# BW1098FFC_USB.net
KiCad netlist of a schematic drawn in Altium Designer
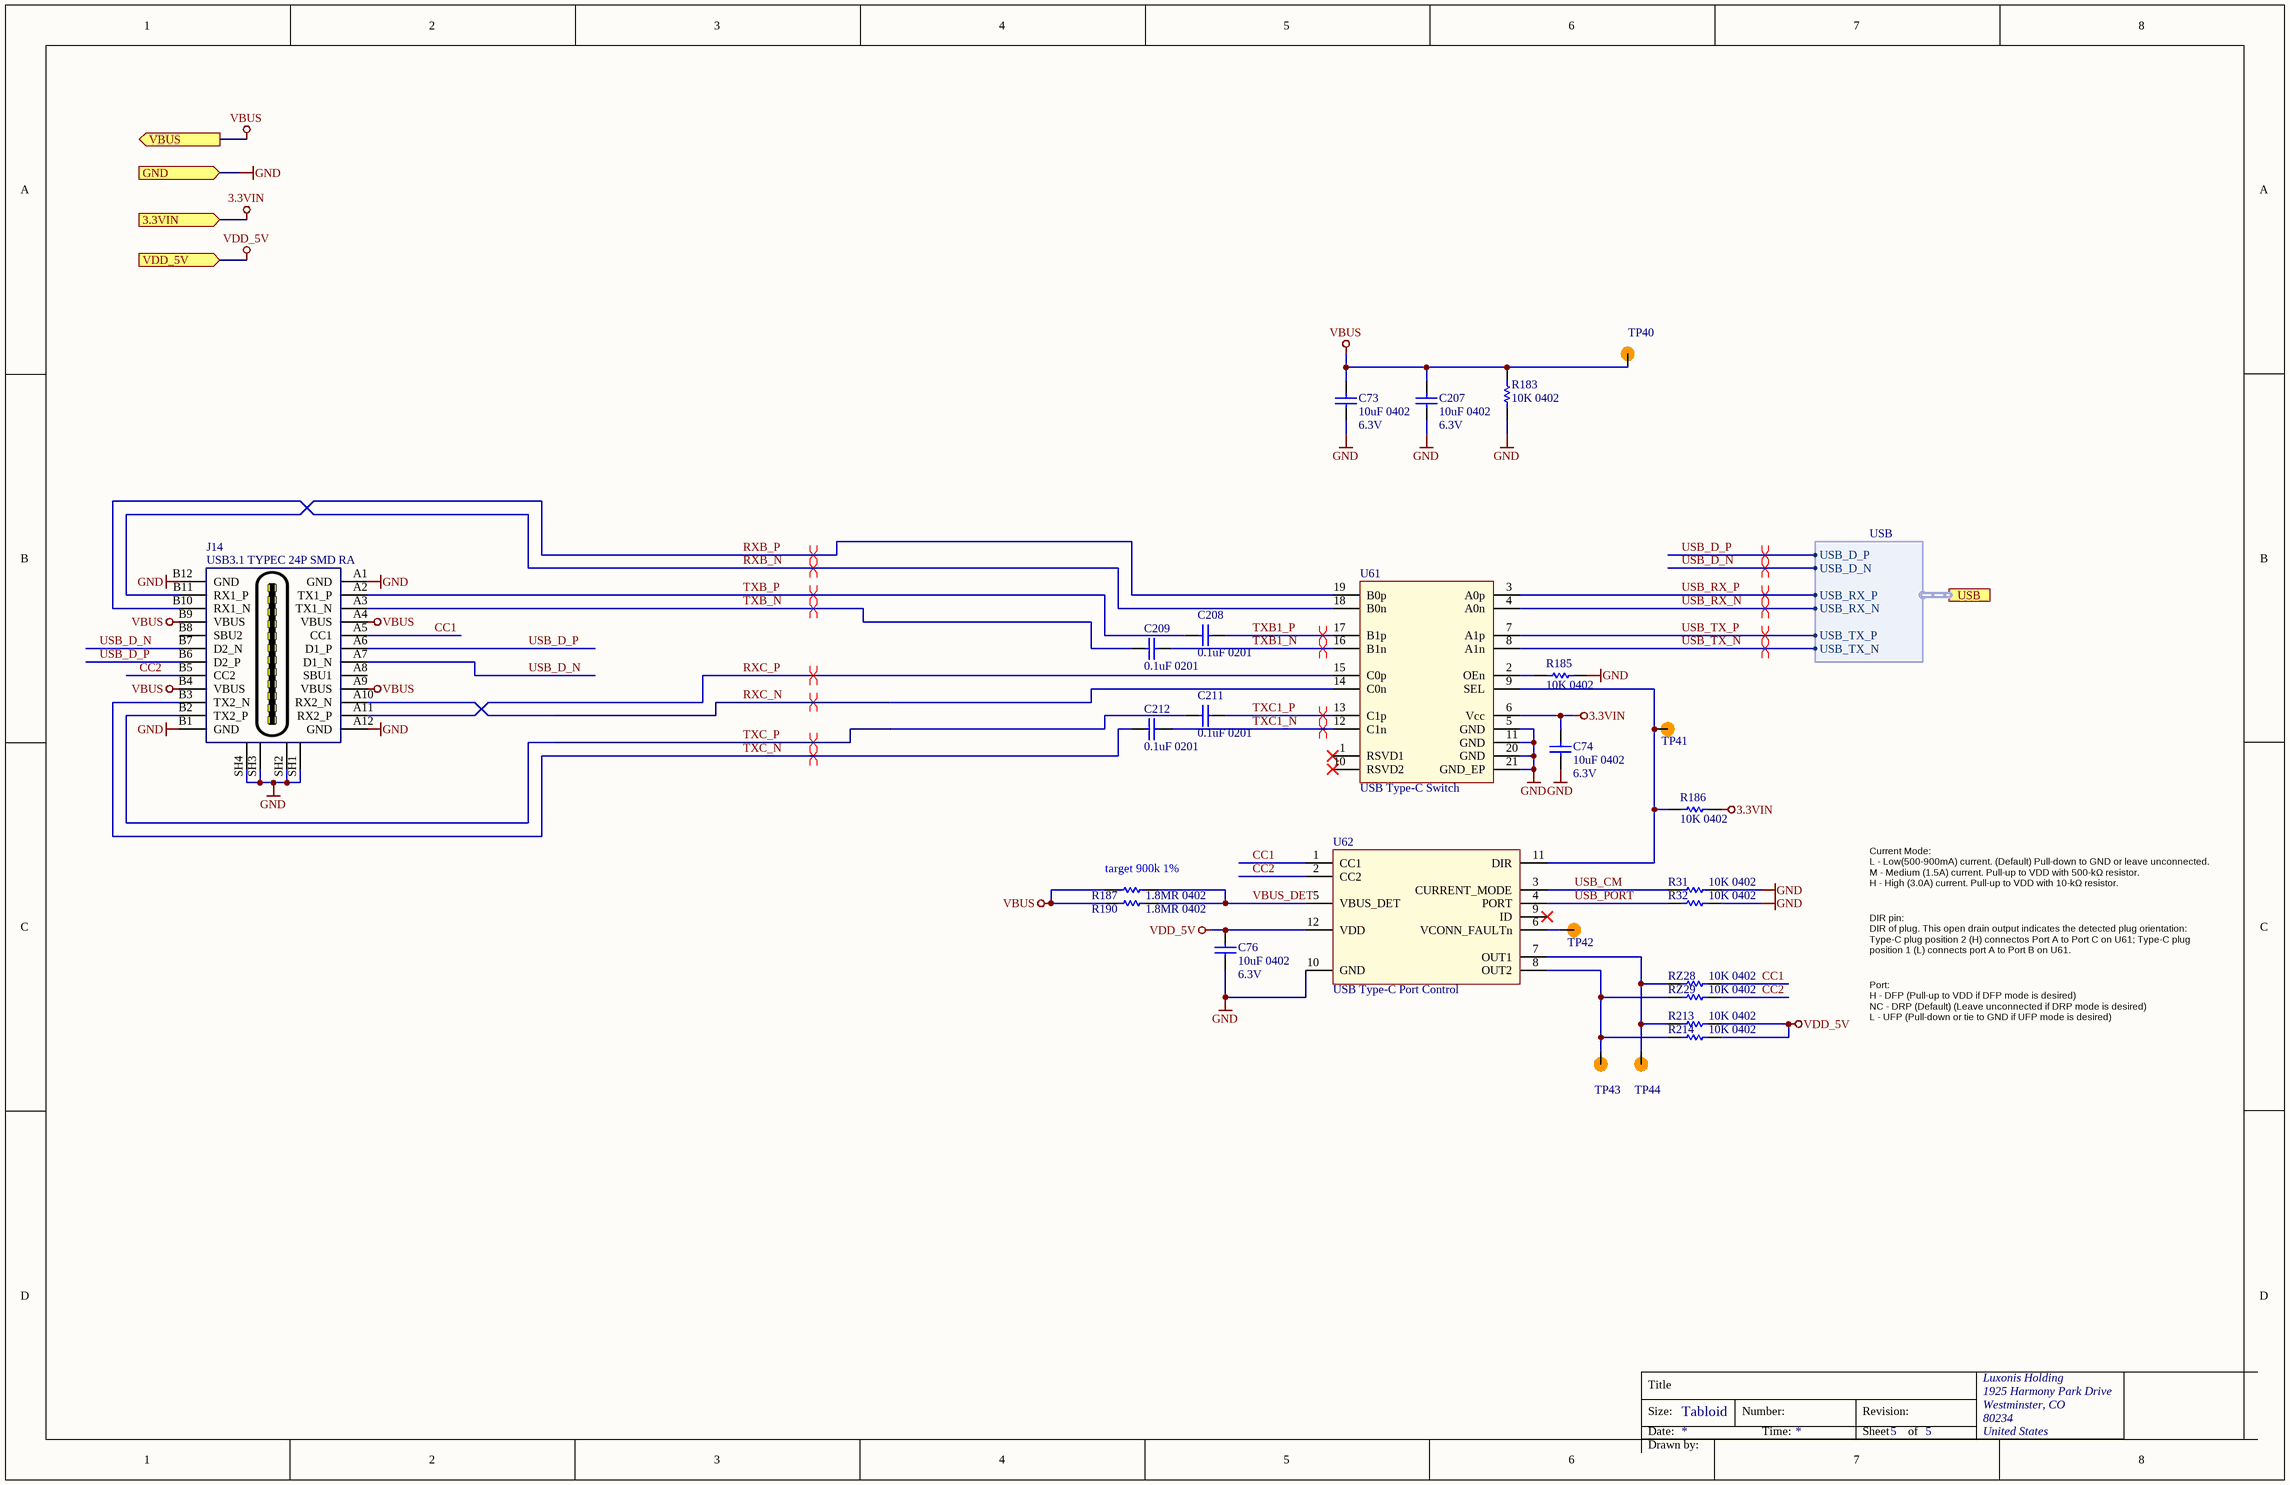
[diagram p0: BW1098FFC_USB.SchDoc]

(export (version "E")
  (design (tool "Eeschema 10.0.6"))
  (components
    (comp (ref "C73")
      (value "10uF 0402")
      (footprint "CAP_Altium_Vault_Generic:CAPC0402(1005)70_N")
      (description "CAP CER 10UF 6.3V X5R 0402 20%")
      (fields (field (name "TOLERANCE") "20%") (field (name "VOLTAGE RATING") "6.3V"))
      (libsource (lib "LuxonisMaster") (part "GRM155R60J106ME15D"))
    )
    (comp (ref "C74")
      (value "10uF 0402")
      (footprint "CAP_Altium_Vault_Generic:CAPC0402(1005)70_N")
      (description "CAP CER 10UF 6.3V X5R 0402 20%")
      (fields (field (name "TOLERANCE") "20%") (field (name "VOLTAGE RATING") "6.3V"))
      (libsource (lib "LuxonisMaster") (part "GRM155R60J106ME15D"))
    )
    (comp (ref "C76")
      (value "10uF 0402")
      (footprint "CAP_Altium_Vault_Generic:CAPC0402(1005)70_N")
      (description "CAP CER 10UF 6.3V X5R 0402 20%")
      (fields (field (name "TOLERANCE") "20%") (field (name "VOLTAGE RATING") "6.3V"))
      (libsource (lib "LuxonisMaster") (part "GRM155R60J106ME15D"))
    )
    (comp (ref "C207")
      (value "10uF 0402")
      (footprint "CAP_Altium_Vault_Generic:CAPC0402(1005)70_N")
      (description "CAP CER 10UF 6.3V X5R 0402 20%")
      (fields (field (name "TOLERANCE") "20%") (field (name "VOLTAGE RATING") "6.3V"))
      (libsource (lib "LuxonisMaster") (part "GRM155R60J106ME15D"))
    )
    (comp (ref "C208")
      (value "0.1uF 0201")
      (footprint "CAP_Altium_Vault_Generic:CAPC0201(0603)33_L")
      (description "CAP CER 0.1UF 10V X5R 0201")
      (fields (field (name "TOLERANCE") "10%") (field (name "VOLTAGE") "10V"))
      (libsource (lib "LuxonisMaster") (part "GRM033R61A104KE15D"))
    )
    (comp (ref "C209")
      (value "0.1uF 0201")
      (footprint "CAP_Altium_Vault_Generic:CAPC0201(0603)33_L")
      (description "CAP CER 0.1UF 10V X5R 0201")
      (fields (field (name "TOLERANCE") "10%") (field (name "VOLTAGE") "10V"))
      (libsource (lib "LuxonisMaster") (part "GRM033R61A104KE15D"))
    )
    (comp (ref "C211")
      (value "0.1uF 0201")
      (footprint "CAP_Altium_Vault_Generic:CAPC0201(0603)33_L")
      (description "CAP CER 0.1UF 10V X5R 0201")
      (fields (field (name "TOLERANCE") "10%") (field (name "VOLTAGE") "10V"))
      (libsource (lib "LuxonisMaster") (part "GRM033R61A104KE15D"))
    )
    (comp (ref "C212")
      (value "0.1uF 0201")
      (footprint "CAP_Altium_Vault_Generic:CAPC0201(0603)33_L")
      (description "CAP CER 0.1UF 10V X5R 0201")
      (fields (field (name "TOLERANCE") "10%") (field (name "VOLTAGE") "10V"))
      (libsource (lib "LuxonisMaster") (part "GRM033R61A104KE15D"))
    )
    (comp (ref "J14")
      (value "USB3.1 TYPEC 24P SMD RA")
      (footprint "LuxonisMaster:105450-0101")
      (description "CONN RCP USB3.1 TYPEC 24P SMD RA")
      (libsource (lib "LuxonisMaster") (part "105450-0101"))
    )
    (comp (ref "R31")
      (value "10K 0402")
      (footprint "RES_Altium_Vault_Generic:RESC0402(1005)_N")
      (fields (field (name "TOLERANCE") "1%"))
      (libsource (lib "LuxonisMaster") (part "RC0402FR-1310KL"))
    )
    (comp (ref "R32")
      (value "10K 0402")
      (footprint "RES_Altium_Vault_Generic:RESC0402(1005)_N")
      (fields (field (name "TOLERANCE") "1%"))
      (libsource (lib "LuxonisMaster") (part "RC0402FR-1310KL"))
    )
    (comp (ref "R183")
      (value "10K 0402")
      (footprint "RES_Altium_Vault_Generic:RESC0402(1005)_N")
      (fields (field (name "TOLERANCE") "1%"))
      (libsource (lib "LuxonisMaster") (part "RC0402FR-1310KL"))
    )
    (comp (ref "R185")
      (value "10K 0402")
      (footprint "RES_Altium_Vault_Generic:RESC0402(1005)_N")
      (fields (field (name "TOLERANCE") "1%"))
      (libsource (lib "LuxonisMaster") (part "RC0402FR-1310KL"))
    )
    (comp (ref "R186")
      (value "10K 0402")
      (footprint "RES_Altium_Vault_Generic:RESC0402(1005)_N")
      (fields (field (name "TOLERANCE") "1%"))
      (libsource (lib "LuxonisMaster") (part "RC0402FR-1310KL"))
    )
    (comp (ref "R187")
      (value "1.8MR 0402")
      (footprint "RES_Altium_Vault_Generic:RESC0402(1005)_N")
      (description "RES SMD 1.8M OHM 1% 1/16W 0402")
      (fields (field (name "TOLERANCE") "1%"))
      (libsource (lib "LuxonisMaster") (part "CRCW04021M80FKED"))
    )
    (comp (ref "R190")
      (value "1.8MR 0402")
      (footprint "RES_Altium_Vault_Generic:RESC0402(1005)_N")
      (description "RES SMD 1.8M OHM 1% 1/16W 0402")
      (fields (field (name "TOLERANCE") "1%"))
      (libsource (lib "LuxonisMaster") (part "CRCW04021M80FKED"))
    )
    (comp (ref "R213")
      (value "10K 0402")
      (footprint "RES_Altium_Vault_Generic:RESC0402(1005)_N")
      (fields (field (name "TOLERANCE") "1%"))
      (libsource (lib "LuxonisMaster") (part "RC0402FR-1310KL"))
    )
    (comp (ref "R214")
      (value "10K 0402")
      (footprint "RES_Altium_Vault_Generic:RESC0402(1005)_N")
      (fields (field (name "TOLERANCE") "1%"))
      (libsource (lib "LuxonisMaster") (part "RC0402FR-1310KL"))
    )
    (comp (ref "RZ28")
      (value "10K 0402")
      (footprint "RES_Altium_Vault_Generic:RESC0402(1005)_N")
      (fields (field (name "TOLERANCE") "1%"))
      (libsource (lib "LuxonisMaster") (part "RC0402FR-1310KL"))
    )
    (comp (ref "RZ29")
      (value "10K 0402")
      (footprint "RES_Altium_Vault_Generic:RESC0402(1005)_N")
      (fields (field (name "TOLERANCE") "1%"))
      (libsource (lib "LuxonisMaster") (part "RC0402FR-1310KL"))
    )
    (comp (ref "TP40")
      (value "TP100_200_NS")
      (footprint "LuxonisMaster:TP100_200_NS")
      (libsource (lib "LuxonisMaster") (part "TEST_POINT"))
    )
    (comp (ref "TP41")
      (value "TP100_200_NS")
      (footprint "LuxonisMaster:TP100_200_NS")
      (libsource (lib "LuxonisMaster") (part "TEST_POINT"))
    )
    (comp (ref "TP42")
      (value "TP100_200_NS")
      (footprint "LuxonisMaster:TP100_200_NS")
      (libsource (lib "LuxonisMaster") (part "TEST_POINT"))
    )
    (comp (ref "TP43")
      (value "TP100_200_NS")
      (footprint "LuxonisMaster:TP100_200_NS")
      (libsource (lib "LuxonisMaster") (part "TEST_POINT"))
    )
    (comp (ref "TP44")
      (value "TP100_200_NS")
      (footprint "LuxonisMaster:TP100_200_NS")
      (libsource (lib "LuxonisMaster") (part "TEST_POINT"))
    )
    (comp (ref "U61")
      (value "USB Type-C Switch")
      (footprint "LuxonisMaster:HD3SS3212RKSR")
      (description "IC MUX 2:1 8 OHM 20VQFN")
      (libsource (lib "LuxonisMaster") (part "HD3SS3212RKSR"))
    )
    (comp (ref "U62")
      (value "USB Type-C Port Control")
      (footprint "LuxonisMaster:TUSB321RWBR")
      (description "IC USB PORT CONTROL TYPE-C 12X2Q")
      (libsource (lib "LuxonisMaster") (part "TUSB321RWBR"))
    )
  )
  (nets
    (net (code "2") (name "/CC1") (class "Default")
      (node (ref "J14") (pin "A5") (pinfunction "CC1_A5") (pintype "passive"))
      (node (ref "RZ28") (pin "2") (pinfunction "2_2") (pintype "passive"))
      (node (ref "U62") (pin "1") (pinfunction "CC1_1") (pintype "passive"))
    )
    (net (code "3") (name "/CC2") (class "Default")
      (node (ref "J14") (pin "B5") (pinfunction "CC2_B5") (pintype "passive"))
      (node (ref "RZ29") (pin "2") (pinfunction "2_2") (pintype "passive"))
      (node (ref "U62") (pin "2") (pinfunction "CC2_2") (pintype "passive"))
    )
    (net (code "4") (name "/RXB_N") (class "Default")
      (node (ref "J14") (pin "B10") (pinfunction "RX1_N_B10") (pintype "passive"))
      (node (ref "U61") (pin "18") (pinfunction "B0n_18") (pintype "passive"))
    )
    (net (code "5") (name "/RXB_P") (class "Default")
      (node (ref "J14") (pin "B11") (pinfunction "RX1_P_B11") (pintype "passive"))
      (node (ref "U61") (pin "19") (pinfunction "B0p_19") (pintype "passive"))
    )
    (net (code "6") (name "/RXC_N") (class "Default")
      (node (ref "J14") (pin "A10") (pinfunction "RX2_N_A10") (pintype "passive"))
      (node (ref "U61") (pin "14") (pinfunction "C0n_14") (pintype "passive"))
    )
    (net (code "7") (name "/RXC_P") (class "Default")
      (node (ref "J14") (pin "A11") (pinfunction "RX2_P_A11") (pintype "passive"))
      (node (ref "U61") (pin "15") (pinfunction "C0p_15") (pintype "passive"))
    )
    (net (code "8") (name "/TXB1_N") (class "Default")
      (node (ref "C209") (pin "2") (pinfunction "2_2") (pintype "passive"))
      (node (ref "U61") (pin "16") (pinfunction "B1n_16") (pintype "passive"))
    )
    (net (code "9") (name "/TXB1_P") (class "Default")
      (node (ref "C208") (pin "2") (pinfunction "2_2") (pintype "passive"))
      (node (ref "U61") (pin "17") (pinfunction "B1p_17") (pintype "passive"))
    )
    (net (code "10") (name "/TXB_N") (class "Default")
      (node (ref "C209") (pin "1") (pinfunction "1_1") (pintype "passive"))
      (node (ref "J14") (pin "A3") (pinfunction "TX1_N_A3") (pintype "passive"))
    )
    (net (code "11") (name "/TXB_P") (class "Default")
      (node (ref "C208") (pin "1") (pinfunction "1_1") (pintype "passive"))
      (node (ref "J14") (pin "A2") (pinfunction "TX1_P_A2") (pintype "passive"))
    )
    (net (code "12") (name "/TXC1_N") (class "Default")
      (node (ref "C212") (pin "2") (pinfunction "2_2") (pintype "passive"))
      (node (ref "U61") (pin "12") (pinfunction "C1n_12") (pintype "passive"))
    )
    (net (code "13") (name "/TXC1_P") (class "Default")
      (node (ref "C211") (pin "2") (pinfunction "2_2") (pintype "passive"))
      (node (ref "U61") (pin "13") (pinfunction "C1p_13") (pintype "passive"))
    )
    (net (code "14") (name "/TXC_N") (class "Default")
      (node (ref "C212") (pin "1") (pinfunction "1_1") (pintype "passive"))
      (node (ref "J14") (pin "B3") (pinfunction "TX2_N_B3") (pintype "passive"))
    )
    (net (code "15") (name "/TXC_P") (class "Default")
      (node (ref "C211") (pin "1") (pinfunction "1_1") (pintype "passive"))
      (node (ref "J14") (pin "B2") (pinfunction "TX2_P_B2") (pintype "passive"))
    )
    (net (code "16") (name "/USB_CM") (class "Default")
      (node (ref "R31") (pin "1") (pinfunction "1_1") (pintype "passive"))
      (node (ref "U62") (pin "3") (pinfunction "CURRENT_MODE_3") (pintype "passive"))
    )
    (net (code "17") (name "/USB_D_N") (class "Default")
      (node (ref "J14") (pin "A7") (pinfunction "D1_N_A7") (pintype "passive"))
      (node (ref "J14") (pin "B7") (pinfunction "D2_N_B7") (pintype "passive"))
    )
    (net (code "18") (name "/USB_D_P") (class "Default")
      (node (ref "J14") (pin "A6") (pinfunction "D1_P_A6") (pintype "passive"))
      (node (ref "J14") (pin "B6") (pinfunction "D2_P_B6") (pintype "passive"))
    )
    (net (code "19") (name "/USB_PORT") (class "Default")
      (node (ref "R32") (pin "1") (pinfunction "1_1") (pintype "passive"))
      (node (ref "U62") (pin "4") (pinfunction "PORT_4") (pintype "passive"))
    )
    (net (code "20") (name "/USB_RX_N") (class "Default")
      (node (ref "U61") (pin "4") (pinfunction "A0n_4") (pintype "passive"))
    )
    (net (code "21") (name "/USB_RX_P") (class "Default")
      (node (ref "U61") (pin "3") (pinfunction "A0p_3") (pintype "passive"))
    )
    (net (code "22") (name "/USB_TX_N") (class "Default")
      (node (ref "U61") (pin "8") (pinfunction "A1n_8") (pintype "passive"))
    )
    (net (code "23") (name "/USB_TX_P") (class "Default")
      (node (ref "U61") (pin "7") (pinfunction "A1p_7") (pintype "passive"))
    )
    (net (code "24") (name "/VBUS_DET") (class "Default")
      (node (ref "R187") (pin "2") (pinfunction "2_2") (pintype "passive"))
      (node (ref "R190") (pin "2") (pinfunction "2_2") (pintype "passive"))
      (node (ref "U62") (pin "5") (pinfunction "VBUS_DET_5") (pintype "passive"))
    )
    (net (code "26") (name "3.3VIN") (class "Default")
      (node (ref "C74") (pin "2") (pinfunction "2_2") (pintype "passive"))
      (node (ref "R186") (pin "2") (pinfunction "2_2") (pintype "passive"))
      (node (ref "U61") (pin "6") (pinfunction "Vcc_6") (pintype "passive"))
    )
    (net (code "27") (name "GND") (class "Default")
      (node (ref "C207") (pin "1") (pinfunction "1_1") (pintype "passive"))
      (node (ref "C73") (pin "1") (pinfunction "1_1") (pintype "passive"))
      (node (ref "C74") (pin "1") (pinfunction "1_1") (pintype "passive"))
      (node (ref "C76") (pin "1") (pinfunction "1_1") (pintype "passive"))
      (node (ref "J14") (pin "A1") (pinfunction "GND_A1") (pintype "passive"))
      (node (ref "J14") (pin "A12") (pinfunction "GND_A12") (pintype "passive"))
      (node (ref "J14") (pin "B1") (pinfunction "GND_B1") (pintype "passive"))
      (node (ref "J14") (pin "B12") (pinfunction "GND_B12") (pintype "passive"))
      (node (ref "J14") (pin "SH1") (pinfunction "SH_SH1") (pintype "passive"))
      (node (ref "J14") (pin "SH2") (pinfunction "SH_SH2") (pintype "passive"))
      (node (ref "J14") (pin "SH3") (pinfunction "SH_SH3") (pintype "passive"))
      (node (ref "J14") (pin "SH4") (pinfunction "SH_SH4") (pintype "passive"))
      (node (ref "R183") (pin "1") (pinfunction "1_1") (pintype "passive"))
      (node (ref "R185") (pin "2") (pinfunction "2_2") (pintype "passive"))
      (node (ref "R31") (pin "2") (pinfunction "2_2") (pintype "passive"))
      (node (ref "R32") (pin "2") (pinfunction "2_2") (pintype "passive"))
      (node (ref "U61") (pin "11") (pinfunction "GND_11") (pintype "passive"))
      (node (ref "U61") (pin "20") (pinfunction "GND_20") (pintype "passive"))
      (node (ref "U61") (pin "21") (pinfunction "GND_EP_21") (pintype "passive"))
      (node (ref "U61") (pin "5") (pinfunction "GND_5") (pintype "passive"))
      (node (ref "U62") (pin "10") (pinfunction "GND_10") (pintype "passive"))
    )
    (net (code "28") (name "Net-(U61-OEn)") (class "Default")
      (node (ref "R185") (pin "1") (pinfunction "1_1") (pintype "passive"))
      (node (ref "U61") (pin "2") (pinfunction "OEn_2") (pintype "passive"))
    )
    (net (code "29") (name "Net-(U61-SEL)") (class "Default")
      (node (ref "R186") (pin "1") (pinfunction "1_1") (pintype "passive"))
      (node (ref "TP41") (pin "1") (pintype "passive"))
      (node (ref "U61") (pin "9") (pinfunction "SEL_9") (pintype "passive"))
      (node (ref "U62") (pin "11") (pinfunction "DIR_11") (pintype "passive"))
    )
    (net (code "30") (name "Net-(U62-OUT1)") (class "Default")
      (node (ref "R213") (pin "1") (pinfunction "1_1") (pintype "passive"))
      (node (ref "RZ28") (pin "1") (pinfunction "1_1") (pintype "passive"))
      (node (ref "TP44") (pin "1") (pintype "passive"))
      (node (ref "U62") (pin "7") (pinfunction "OUT1_7") (pintype "passive"))
    )
    (net (code "31") (name "Net-(U62-OUT2)") (class "Default")
      (node (ref "R214") (pin "1") (pinfunction "1_1") (pintype "passive"))
      (node (ref "RZ29") (pin "1") (pinfunction "1_1") (pintype "passive"))
      (node (ref "TP43") (pin "1") (pintype "passive"))
      (node (ref "U62") (pin "8") (pinfunction "OUT2_8") (pintype "passive"))
    )
    (net (code "32") (name "Net-(U62-VCONN_FAULTn)") (class "Default")
      (node (ref "TP42") (pin "1") (pintype "passive"))
      (node (ref "U62") (pin "6") (pinfunction "VCONN_FAULTn_6") (pintype "passive"))
    )
    (net (code "33") (name "VBUS") (class "Default")
      (node (ref "C207") (pin "2") (pinfunction "2_2") (pintype "passive"))
      (node (ref "C73") (pin "2") (pinfunction "2_2") (pintype "passive"))
      (node (ref "J14") (pin "A4") (pinfunction "VBUS_A4") (pintype "passive"))
      (node (ref "J14") (pin "A9") (pinfunction "VBUS_A9") (pintype "passive"))
      (node (ref "J14") (pin "B4") (pinfunction "VBUS_B4") (pintype "passive"))
      (node (ref "J14") (pin "B9") (pinfunction "VBUS_B9") (pintype "passive"))
      (node (ref "R183") (pin "2") (pinfunction "2_2") (pintype "passive"))
      (node (ref "R187") (pin "1") (pinfunction "1_1") (pintype "passive"))
      (node (ref "R190") (pin "1") (pinfunction "1_1") (pintype "passive"))
      (node (ref "TP40") (pin "1") (pintype "passive"))
    )
    (net (code "34") (name "VDD_5V") (class "Default")
      (node (ref "C76") (pin "2") (pinfunction "2_2") (pintype "passive"))
      (node (ref "R213") (pin "2") (pinfunction "2_2") (pintype "passive"))
      (node (ref "R214") (pin "2") (pinfunction "2_2") (pintype "passive"))
      (node (ref "U62") (pin "12") (pinfunction "VDD_12") (pintype "passive"))
    )
    (net (code "35") (name "unconnected-(J14-SBU1-PadA8)") (class "Default")
      (node (ref "J14") (pin "A8") (pinfunction "SBU1_A8") (pintype "passive"))
    )
    (net (code "36") (name "unconnected-(J14-SBU2-PadB8)") (class "Default")
      (node (ref "J14") (pin "B8") (pinfunction "SBU2_B8") (pintype "passive"))
    )
    (net (code "37") (name "unconnected-(U61-RSVD1-Pad1)") (class "Default")
      (node (ref "U61") (pin "1") (pinfunction "RSVD1_1") (pintype "passive+no_connect"))
    )
    (net (code "38") (name "unconnected-(U61-RSVD2-Pad10)") (class "Default")
      (node (ref "U61") (pin "10") (pinfunction "RSVD2_10") (pintype "passive+no_connect"))
    )
    (net (code "39") (name "unconnected-(U62-ID-Pad9)") (class "Default")
      (node (ref "U62") (pin "9") (pinfunction "ID_9") (pintype "passive+no_connect"))
    )
  )
)
